# MCU_Powers.net
KiCad netlist of a schematic drawn in Altium Designer
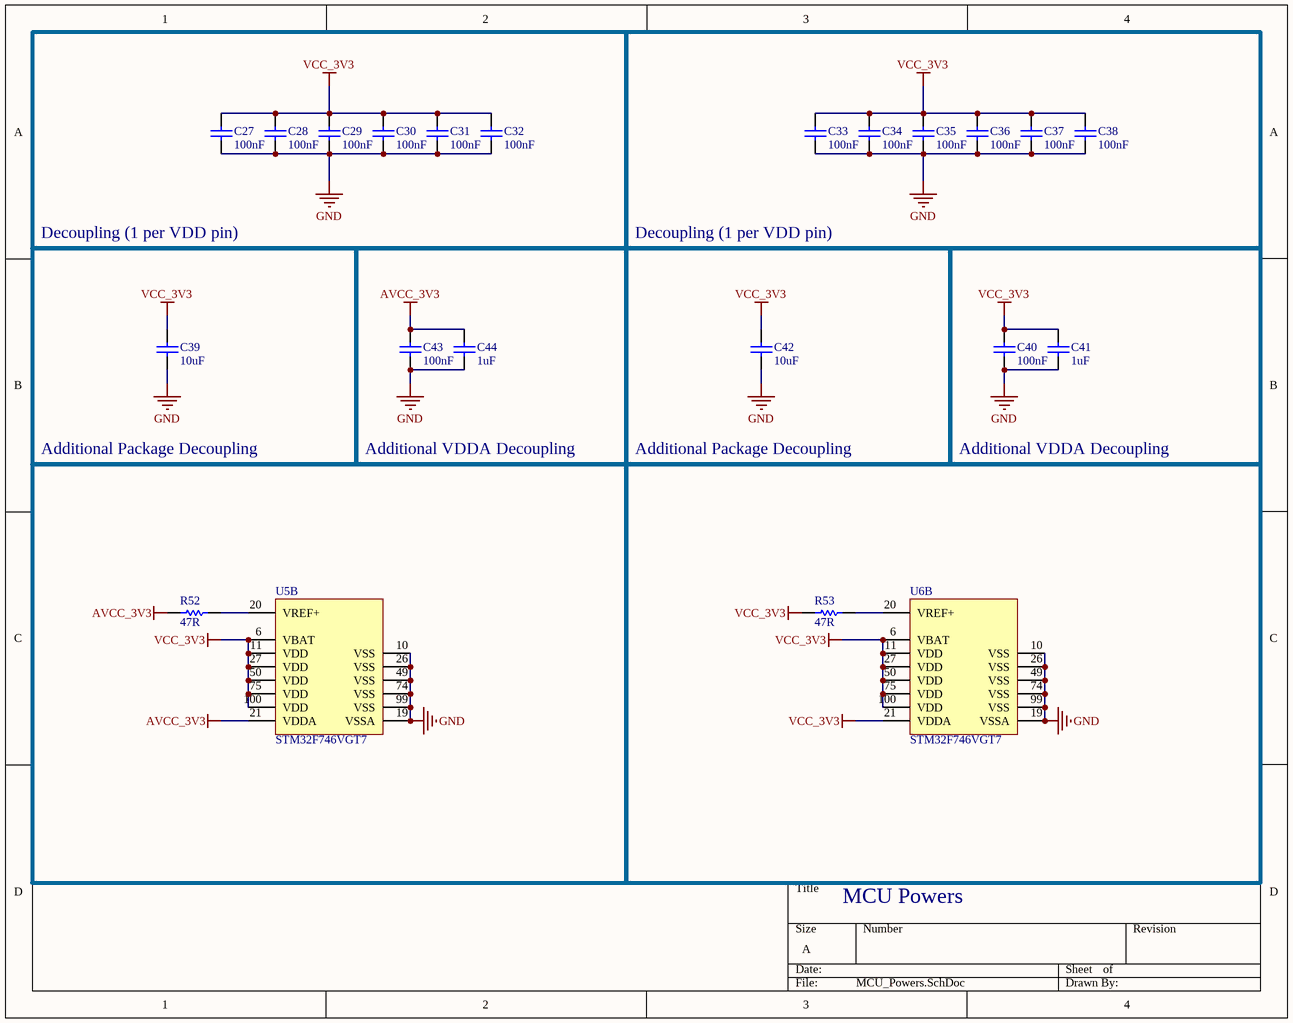
[diagram p0: MCU_Powers.SchDoc]

(export (version "E")
  (design (tool "Eeschema 10.0.6"))
  (components
    (comp (ref "C27")
      (value "100nF")
      (footprint "CAPC0603(1608)100_N")
      (description "CAP 100nF 10V ±10% 0603 (1608 Metric) Thickness 1mm SMD")
      (fields (field (name "TOLERANCE") "Â±10%"))
      (libsource (lib "Altium Content Vault") (part "CMP-1035-02580-1"))
    )
    (comp (ref "C28")
      (value "100nF")
      (footprint "CAPC0603(1608)100_N")
      (description "CAP 100nF 10V ±10% 0603 (1608 Metric) Thickness 1mm SMD")
      (fields (field (name "TOLERANCE") "Â±10%"))
      (libsource (lib "Altium Content Vault") (part "CAP"))
    )
    (comp (ref "C29")
      (value "100nF")
      (footprint "CAPC0603(1608)100_N")
      (description "CAP 100nF 10V ±10% 0603 (1608 Metric) Thickness 1mm SMD")
      (fields (field (name "TOLERANCE") "Â±10%"))
      (libsource (lib "Altium Content Vault") (part "CAP"))
    )
    (comp (ref "C30")
      (value "100nF")
      (footprint "CAPC0603(1608)100_N")
      (description "CAP 100nF 10V ±10% 0603 (1608 Metric) Thickness 1mm SMD")
      (fields (field (name "TOLERANCE") "Â±10%"))
      (libsource (lib "Altium Content Vault") (part "CAP"))
    )
    (comp (ref "C31")
      (value "100nF")
      (footprint "CAPC0603(1608)100_N")
      (description "CAP 100nF 10V ±10% 0603 (1608 Metric) Thickness 1mm SMD")
      (fields (field (name "TOLERANCE") "Â±10%"))
      (libsource (lib "Altium Content Vault") (part "CAP"))
    )
    (comp (ref "C32")
      (value "100nF")
      (footprint "CAPC0603(1608)100_N")
      (description "CAP 100nF 10V ±10% 0603 (1608 Metric) Thickness 1mm SMD")
      (fields (field (name "TOLERANCE") "Â±10%"))
      (libsource (lib "Altium Content Vault") (part "CAP"))
    )
    (comp (ref "C33")
      (value "100nF")
      (footprint "CAPC0603(1608)100_N")
      (description "CAP 100nF 10V ±10% 0603 (1608 Metric) Thickness 1mm SMD")
      (fields (field (name "TOLERANCE") "Â±10%"))
      (libsource (lib "Altium Content Vault") (part "CMP-1035-02580-1"))
    )
    (comp (ref "C34")
      (value "100nF")
      (footprint "CAPC0603(1608)100_N")
      (description "CAP 100nF 10V ±10% 0603 (1608 Metric) Thickness 1mm SMD")
      (fields (field (name "TOLERANCE") "Â±10%"))
      (libsource (lib "Altium Content Vault") (part "CAP"))
    )
    (comp (ref "C35")
      (value "100nF")
      (footprint "CAPC0603(1608)100_N")
      (description "CAP 100nF 10V ±10% 0603 (1608 Metric) Thickness 1mm SMD")
      (fields (field (name "TOLERANCE") "Â±10%"))
      (libsource (lib "Altium Content Vault") (part "CAP"))
    )
    (comp (ref "C36")
      (value "100nF")
      (footprint "CAPC0603(1608)100_N")
      (description "CAP 100nF 10V ±10% 0603 (1608 Metric) Thickness 1mm SMD")
      (fields (field (name "TOLERANCE") "Â±10%"))
      (libsource (lib "Altium Content Vault") (part "CAP"))
    )
    (comp (ref "C37")
      (value "100nF")
      (footprint "CAPC0603(1608)100_N")
      (description "CAP 100nF 10V ±10% 0603 (1608 Metric) Thickness 1mm SMD")
      (fields (field (name "TOLERANCE") "Â±10%"))
      (libsource (lib "Altium Content Vault") (part "CAP"))
    )
    (comp (ref "C38")
      (value "100nF")
      (footprint "CAPC0603(1608)100_N")
      (description "CAP 100nF 10V ±10% 0603 (1608 Metric) Thickness 1mm SMD")
      (fields (field (name "TOLERANCE") "Â±10%"))
      (libsource (lib "Altium Content Vault") (part "CAP"))
    )
    (comp (ref "C39")
      (value "10uF")
      (footprint "CAPC0603(1608)100_N")
      (description "CAP 10uF 10V ±10% 0603 (1608 Metric) Thickness 1mm SMD")
      (fields (field (name "TOLERANCE") "Â±10%"))
      (libsource (lib "Altium Content Vault") (part "CAP"))
    )
    (comp (ref "C40")
      (value "100nF")
      (footprint "CAPC0603(1608)100_N")
      (description "CAP 100nF 10V ±10% 0603 (1608 Metric) Thickness 1mm SMD")
      (fields (field (name "TOLERANCE") "Â±10%"))
      (libsource (lib "Altium Content Vault") (part "CAP"))
    )
    (comp (ref "C41")
      (value "1uF")
      (footprint "CAPC0603(1608)100_N")
      (description "CAP 1uF 10V ±10% 0603 (1608 Metric) Thickness 1mm SMD")
      (fields (field (name "TOLERANCE") "Â±10%"))
      (libsource (lib "Altium Content Vault") (part "CAP"))
    )
    (comp (ref "C42")
      (value "10uF")
      (footprint "CAPC0603(1608)100_N")
      (description "CAP 10uF 10V ±10% 0603 (1608 Metric) Thickness 1mm SMD")
      (fields (field (name "TOLERANCE") "Â±10%"))
      (libsource (lib "Altium Content Vault") (part "CAP"))
    )
    (comp (ref "C43")
      (value "100nF")
      (footprint "CAPC0603(1608)100_N")
      (description "CAP 100nF 10V ±10% 0603 (1608 Metric) Thickness 1mm SMD")
      (fields (field (name "TOLERANCE") "Â±10%"))
      (libsource (lib "Altium Content Vault") (part "CAP"))
    )
    (comp (ref "C44")
      (value "1uF")
      (footprint "CAPC0603(1608)100_N")
      (description "CAP 1uF 10V ±10% 0603 (1608 Metric) Thickness 1mm SMD")
      (fields (field (name "TOLERANCE") "Â±10%"))
      (libsource (lib "Altium Content Vault") (part "CAP"))
    )
    (comp (ref "R52")
      (value "47R")
      (footprint "RESC0603(1608)_N")
      (description "47R 0.1W 1% 0603 (1608 Metric)  SMD")
      (fields (field (name "POWER") "0.1 W") (field (name "TOLERANCE") "1 %"))
      (libsource (lib "Altium Content Vault") (part "RES"))
    )
    (comp (ref "R53")
      (value "47R")
      (footprint "RESC0603(1608)_N")
      (description "47R 0.1W 1% 0603 (1608 Metric)  SMD")
      (fields (field (name "POWER") "0.1 W") (field (name "TOLERANCE") "1 %"))
      (libsource (lib "Altium Content Vault") (part "RES"))
    )
    (comp (ref "U5")
      (value "STM32F746VGT7")
      (footprint "STM-LQFP100_L")
      (libsource (lib "Altium Content Vault") (part "MC-ARM-STM32F7X6-LQFP100"))
    )
    (comp (ref "U6")
      (value "STM32F746VGT7")
      (footprint "STM-LQFP100_L")
      (libsource (lib "Altium Content Vault") (part "MC-ARM-STM32F7X6-LQFP100"))
    )
  )
  (nets
    (net (code "1") (name "AVCC_3V3") (class "Default")
      (node (ref "C43") (pin "2") (pinfunction "2_2") (pintype "passive"))
      (node (ref "C44") (pin "2") (pinfunction "2_2") (pintype "passive"))
      (node (ref "R52") (pin "1") (pinfunction "1_1") (pintype "passive"))
      (node (ref "U5") (pin "21") (pinfunction "VDDA_21") (pintype "power_in"))
    )
    (net (code "2") (name "GND") (class "Default")
      (node (ref "C27") (pin "1") (pinfunction "1_1") (pintype "passive"))
      (node (ref "C28") (pin "1") (pinfunction "1_1") (pintype "passive"))
      (node (ref "C29") (pin "1") (pinfunction "1_1") (pintype "passive"))
      (node (ref "C30") (pin "1") (pinfunction "1_1") (pintype "passive"))
      (node (ref "C31") (pin "1") (pinfunction "1_1") (pintype "passive"))
      (node (ref "C32") (pin "1") (pinfunction "1_1") (pintype "passive"))
      (node (ref "C33") (pin "1") (pinfunction "1_1") (pintype "passive"))
      (node (ref "C34") (pin "1") (pinfunction "1_1") (pintype "passive"))
      (node (ref "C35") (pin "1") (pinfunction "1_1") (pintype "passive"))
      (node (ref "C36") (pin "1") (pinfunction "1_1") (pintype "passive"))
      (node (ref "C37") (pin "1") (pinfunction "1_1") (pintype "passive"))
      (node (ref "C38") (pin "1") (pinfunction "1_1") (pintype "passive"))
      (node (ref "C39") (pin "1") (pinfunction "1_1") (pintype "passive"))
      (node (ref "C40") (pin "1") (pinfunction "1_1") (pintype "passive"))
      (node (ref "C41") (pin "1") (pinfunction "1_1") (pintype "passive"))
      (node (ref "C42") (pin "1") (pinfunction "1_1") (pintype "passive"))
      (node (ref "C43") (pin "1") (pinfunction "1_1") (pintype "passive"))
      (node (ref "C44") (pin "1") (pinfunction "1_1") (pintype "passive"))
      (node (ref "U5") (pin "10") (pinfunction "VSS_10") (pintype "power_in"))
      (node (ref "U5") (pin "19") (pinfunction "VSSA_19") (pintype "power_in"))
      (node (ref "U5") (pin "26") (pinfunction "VSS_26") (pintype "power_in"))
      (node (ref "U5") (pin "49") (pinfunction "VSS_49") (pintype "power_in"))
      (node (ref "U5") (pin "74") (pinfunction "VSS_74") (pintype "power_in"))
      (node (ref "U5") (pin "99") (pinfunction "VSS_99") (pintype "power_in"))
      (node (ref "U6") (pin "10") (pinfunction "VSS_10") (pintype "power_in"))
      (node (ref "U6") (pin "19") (pinfunction "VSSA_19") (pintype "power_in"))
      (node (ref "U6") (pin "26") (pinfunction "VSS_26") (pintype "power_in"))
      (node (ref "U6") (pin "49") (pinfunction "VSS_49") (pintype "power_in"))
      (node (ref "U6") (pin "74") (pinfunction "VSS_74") (pintype "power_in"))
      (node (ref "U6") (pin "99") (pinfunction "VSS_99") (pintype "power_in"))
    )
    (net (code "3") (name "Net-(U5B-VREF+)") (class "Default")
      (node (ref "R52") (pin "2") (pinfunction "2_2") (pintype "passive"))
      (node (ref "U5") (pin "20") (pinfunction "VREF+_20") (pintype "power_in"))
    )
    (net (code "4") (name "Net-(U6B-VREF+)") (class "Default")
      (node (ref "R53") (pin "2") (pinfunction "2_2") (pintype "passive"))
      (node (ref "U6") (pin "20") (pinfunction "VREF+_20") (pintype "power_in"))
    )
    (net (code "5") (name "VCC_3V3") (class "Default")
      (node (ref "C27") (pin "2") (pinfunction "2_2") (pintype "passive"))
      (node (ref "C28") (pin "2") (pinfunction "2_2") (pintype "passive"))
      (node (ref "C29") (pin "2") (pinfunction "2_2") (pintype "passive"))
      (node (ref "C30") (pin "2") (pinfunction "2_2") (pintype "passive"))
      (node (ref "C31") (pin "2") (pinfunction "2_2") (pintype "passive"))
      (node (ref "C32") (pin "2") (pinfunction "2_2") (pintype "passive"))
      (node (ref "C33") (pin "2") (pinfunction "2_2") (pintype "passive"))
      (node (ref "C34") (pin "2") (pinfunction "2_2") (pintype "passive"))
      (node (ref "C35") (pin "2") (pinfunction "2_2") (pintype "passive"))
      (node (ref "C36") (pin "2") (pinfunction "2_2") (pintype "passive"))
      (node (ref "C37") (pin "2") (pinfunction "2_2") (pintype "passive"))
      (node (ref "C38") (pin "2") (pinfunction "2_2") (pintype "passive"))
      (node (ref "C39") (pin "2") (pinfunction "2_2") (pintype "passive"))
      (node (ref "C40") (pin "2") (pinfunction "2_2") (pintype "passive"))
      (node (ref "C41") (pin "2") (pinfunction "2_2") (pintype "passive"))
      (node (ref "C42") (pin "2") (pinfunction "2_2") (pintype "passive"))
      (node (ref "R53") (pin "1") (pinfunction "1_1") (pintype "passive"))
      (node (ref "U5") (pin "100") (pinfunction "VDD_100") (pintype "power_in"))
      (node (ref "U5") (pin "11") (pinfunction "VDD_11") (pintype "power_in"))
      (node (ref "U5") (pin "27") (pinfunction "VDD_27") (pintype "power_in"))
      (node (ref "U5") (pin "50") (pinfunction "VDD_50") (pintype "power_in"))
      (node (ref "U5") (pin "6") (pinfunction "VBAT_6") (pintype "power_in"))
      (node (ref "U5") (pin "75") (pinfunction "VDD_75") (pintype "power_in"))
      (node (ref "U6") (pin "100") (pinfunction "VDD_100") (pintype "power_in"))
      (node (ref "U6") (pin "11") (pinfunction "VDD_11") (pintype "power_in"))
      (node (ref "U6") (pin "21") (pinfunction "VDDA_21") (pintype "power_in"))
      (node (ref "U6") (pin "27") (pinfunction "VDD_27") (pintype "power_in"))
      (node (ref "U6") (pin "50") (pinfunction "VDD_50") (pintype "power_in"))
      (node (ref "U6") (pin "6") (pinfunction "VBAT_6") (pintype "power_in"))
      (node (ref "U6") (pin "75") (pinfunction "VDD_75") (pintype "power_in"))
    )
  )
)
